# LSPACE-PCB.net
KiCad netlist of a schematic drawn in EAGLE
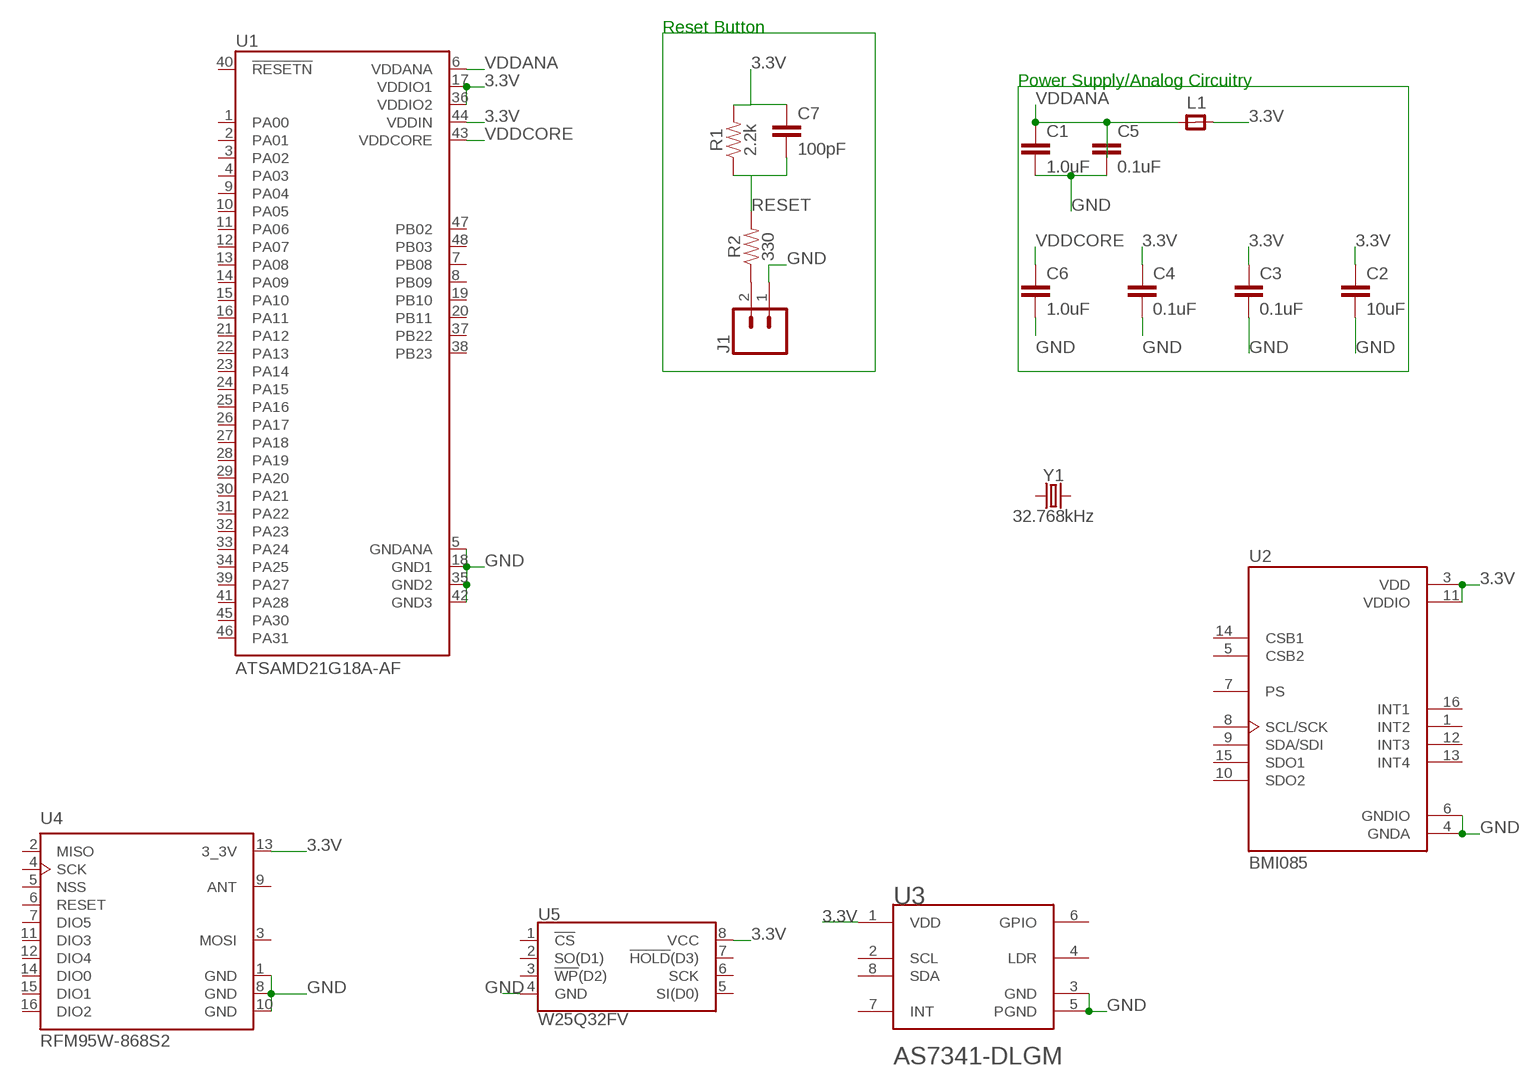
[diagram p0: schematic, sheet 1]

(export (version "E")
  (design (tool "Eeschema 10.0.6"))
  (components
    (comp (ref "C1")
      (value "1.0uF")
      (footprint "eagle-import:1206")
      (libsource (lib "eagle-import") (part "1.0UF-1206-50V-10%"))
    )
    (comp (ref "C2")
      (value "10uF")
      (footprint "eagle-import:1206")
      (libsource (lib "eagle-import") (part "10UF-1206-6.3V-20%"))
    )
    (comp (ref "C3")
      (value "0.1uF")
      (footprint "eagle-import:0603")
      (libsource (lib "eagle-import") (part "0.1UF-0603-100V-10%"))
    )
    (comp (ref "C4")
      (value "0.1uF")
      (footprint "eagle-import:0603")
      (libsource (lib "eagle-import") (part "0.1UF-0603-100V-10%"))
    )
    (comp (ref "C5")
      (value "0.1uF")
      (footprint "eagle-import:0603")
      (libsource (lib "eagle-import") (part "0.1UF-0603-100V-10%"))
    )
    (comp (ref "C6")
      (value "1.0uF")
      (footprint "eagle-import:1206")
      (libsource (lib "eagle-import") (part "1.0UF-1206-50V-10%"))
    )
    (comp (ref "C7")
      (value "100pF")
      (footprint "eagle-import:0603")
      (libsource (lib "eagle-import") (part "100PF-0603-50V-5%"))
    )
    (comp (ref "J1")
      (value "CONN_02")
      (footprint "eagle-import:1X02")
      (libsource (lib "eagle-import") (part "CONN_02"))
    )
    (comp (ref "L1")
      (value "RC-MASTER-SMD_FB_1206MP")
      (footprint "eagle-import:RC-MASTER-SMD_L1206MP")
      (libsource (lib "eagle-import") (part "RC-MASTER-SMD_FB_1206MP"))
    )
    (comp (ref "R1")
      (value "2.2k")
      (footprint "eagle-import:0603")
      (libsource (lib "eagle-import") (part "2.2KOHM-0603-1/10W-1%"))
    )
    (comp (ref "R2")
      (value "330")
      (footprint "eagle-import:0603")
      (libsource (lib "eagle-import") (part "330OHM-0603-1/10W-1%"))
    )
    (comp (ref "U1")
      (value "ATSAMD21G18A-AF")
      (footprint "eagle-import:QFP50P900X900X120-48N")
      (fields (field (name "MF") "Microchip Technology / Atmel"))
      (libsource (lib "eagle-import") (part "ATSAMD21G18A-AF"))
    )
    (comp (ref "U2")
      (value "BMI085")
      (footprint "eagle-import:PQFN50P450X300X100-16N")
      (fields (field (name "MF") "Bosch Sensortec"))
      (libsource (lib "eagle-import") (part "BMI085"))
    )
    (comp (ref "U3")
      (value "AMS_AS7341-DLGMAMS_AS7341-DLGM_0_0")
      (footprint "eagle-import:AMS_AS7341-DLGM_0")
      (fields
        (field (name "DIGIKEY_PART_NUMBER") "AS7341-DLGMCT-ND")
        (field (name "MF") "ams")
        (field (name "MOUSER_PART_NUMBER") "985-AS7341-DLGM")
      )
      (libsource (lib "eagle-import") (part "AMS_AS7341-DLGMAMS_AS7341-DLGM_0_0"))
    )
    (comp (ref "U4")
      (value "RFM95W-868S2")
      (footprint "eagle-import:XCVR_RFM95W-868S2")
      (fields (field (name "MF") "RF"))
      (libsource (lib "eagle-import") (part "RFM95W-868S2"))
    )
    (comp (ref "U5")
      (value "W25Q32FV")
      (footprint "eagle-import:SOIC-8")
      (libsource (lib "eagle-import") (part "W25Q32FVSS"))
    )
    (comp (ref "Y1")
      (value "32.768kHz")
      (footprint "eagle-import:CRYSTAL-SMD-3.2X1.5MM")
      (libsource (lib "eagle-import") (part "CRYSTAL-32.768KHZSMD-3.2X1.5"))
    )
  )
  (nets
    (net (code "1") (name "/3.3V") (class "Default")
      (node (ref "C2") (pin "1") (pinfunction "1_1") (pintype "passive"))
      (node (ref "C3") (pin "1") (pinfunction "1_1") (pintype "passive"))
      (node (ref "C4") (pin "1") (pinfunction "1_1") (pintype "passive"))
      (node (ref "C7") (pin "1") (pinfunction "1_1") (pintype "passive"))
      (node (ref "L1") (pin "2") (pinfunction "2_2") (pintype "passive"))
      (node (ref "R1") (pin "2") (pinfunction "2_2") (pintype "passive"))
      (node (ref "U1") (pin "17") (pinfunction "VDDIO1_17") (pintype "power_in"))
      (node (ref "U1") (pin "36") (pinfunction "VDDIO2_36") (pintype "power_in"))
      (node (ref "U1") (pin "44") (pinfunction "VDDIN_44") (pintype "power_in"))
      (node (ref "U2") (pin "11") (pinfunction "VDDIO_11") (pintype "power_in"))
      (node (ref "U2") (pin "3") (pinfunction "VDD_3") (pintype "power_in"))
      (node (ref "U3") (pin "1") (pinfunction "VDD_1") (pintype "power_in"))
      (node (ref "U4") (pin "13") (pinfunction "3_3V_13") (pintype "power_in"))
      (node (ref "U5") (pin "8") (pinfunction "VCC_8") (pintype "bidirectional"))
    )
    (net (code "2") (name "/GND") (class "Default")
      (node (ref "C1") (pin "2") (pinfunction "2_2") (pintype "passive"))
      (node (ref "C2") (pin "2") (pinfunction "2_2") (pintype "passive"))
      (node (ref "C3") (pin "2") (pinfunction "2_2") (pintype "passive"))
      (node (ref "C4") (pin "2") (pinfunction "2_2") (pintype "passive"))
      (node (ref "C5") (pin "2") (pinfunction "2_2") (pintype "passive"))
      (node (ref "C6") (pin "2") (pinfunction "2_2") (pintype "passive"))
      (node (ref "J1") (pin "1") (pinfunction "1_1") (pintype "passive"))
      (node (ref "U1") (pin "18") (pinfunction "GND1_18") (pintype "power_in"))
      (node (ref "U1") (pin "35") (pinfunction "GND2_35") (pintype "power_in"))
      (node (ref "U1") (pin "42") (pinfunction "GND3_42") (pintype "power_in"))
      (node (ref "U1") (pin "5") (pinfunction "GNDANA_5") (pintype "power_in"))
      (node (ref "U2") (pin "4") (pinfunction "GNDA_4") (pintype "power_in"))
      (node (ref "U2") (pin "6") (pinfunction "GNDIO_6") (pintype "power_in"))
      (node (ref "U3") (pin "3") (pinfunction "GND_3") (pintype "power_in"))
      (node (ref "U3") (pin "5") (pinfunction "PGND_5") (pintype "power_in"))
      (node (ref "U4") (pin "1") (pinfunction "GND_1") (pintype "power_in"))
      (node (ref "U4") (pin "10") (pinfunction "GND_10") (pintype "power_in"))
      (node (ref "U4") (pin "8") (pinfunction "GND_8") (pintype "power_in"))
      (node (ref "U5") (pin "4") (pinfunction "GND_4") (pintype "bidirectional"))
    )
    (net (code "3") (name "/RESET") (class "Default")
      (node (ref "C7") (pin "2") (pinfunction "2_2") (pintype "passive"))
      (node (ref "R1") (pin "1") (pinfunction "1_1") (pintype "passive"))
      (node (ref "R2") (pin "2") (pinfunction "2_2") (pintype "passive"))
    )
    (net (code "4") (name "/VDDANA") (class "Default")
      (node (ref "C1") (pin "1") (pinfunction "1_1") (pintype "passive"))
      (node (ref "C5") (pin "1") (pinfunction "1_1") (pintype "passive"))
      (node (ref "L1") (pin "1") (pinfunction "1_1") (pintype "passive"))
      (node (ref "U1") (pin "6") (pinfunction "VDDANA_6") (pintype "power_in"))
    )
    (net (code "5") (name "/VDDCORE") (class "Default")
      (node (ref "C6") (pin "1") (pinfunction "1_1") (pintype "passive"))
      (node (ref "U1") (pin "43") (pinfunction "VDDCORE_43") (pintype "power_in"))
    )
    (net (code "6") (name "Net-(J1-Pad2)") (class "Default")
      (node (ref "J1") (pin "2") (pinfunction "2_2") (pintype "passive"))
      (node (ref "R2") (pin "1") (pinfunction "1_1") (pintype "passive"))
    )
    (net (code "7") (name "unconnected-(U1-PA00-Pad1)") (class "Default")
      (node (ref "U1") (pin "1") (pinfunction "PA00_1") (pintype "bidirectional"))
    )
    (net (code "8") (name "unconnected-(U1-PA01-Pad2)") (class "Default")
      (node (ref "U1") (pin "2") (pinfunction "PA01_2") (pintype "bidirectional"))
    )
    (net (code "9") (name "unconnected-(U1-PA02-Pad3)") (class "Default")
      (node (ref "U1") (pin "3") (pinfunction "PA02_3") (pintype "bidirectional"))
    )
    (net (code "10") (name "unconnected-(U1-PA03-Pad4)") (class "Default")
      (node (ref "U1") (pin "4") (pinfunction "PA03_4") (pintype "bidirectional"))
    )
    (net (code "11") (name "unconnected-(U1-PA04-Pad9)") (class "Default")
      (node (ref "U1") (pin "9") (pinfunction "PA04_9") (pintype "bidirectional"))
    )
    (net (code "12") (name "unconnected-(U1-PA05-Pad10)") (class "Default")
      (node (ref "U1") (pin "10") (pinfunction "PA05_10") (pintype "bidirectional"))
    )
    (net (code "13") (name "unconnected-(U1-PA06-Pad11)") (class "Default")
      (node (ref "U1") (pin "11") (pinfunction "PA06_11") (pintype "bidirectional"))
    )
    (net (code "14") (name "unconnected-(U1-PA07-Pad12)") (class "Default")
      (node (ref "U1") (pin "12") (pinfunction "PA07_12") (pintype "bidirectional"))
    )
    (net (code "15") (name "unconnected-(U1-PA08-Pad13)") (class "Default")
      (node (ref "U1") (pin "13") (pinfunction "PA08_13") (pintype "bidirectional"))
    )
    (net (code "16") (name "unconnected-(U1-PA09-Pad14)") (class "Default")
      (node (ref "U1") (pin "14") (pinfunction "PA09_14") (pintype "bidirectional"))
    )
    (net (code "17") (name "unconnected-(U1-PA10-Pad15)") (class "Default")
      (node (ref "U1") (pin "15") (pinfunction "PA10_15") (pintype "bidirectional"))
    )
    (net (code "18") (name "unconnected-(U1-PA11-Pad16)") (class "Default")
      (node (ref "U1") (pin "16") (pinfunction "PA11_16") (pintype "bidirectional"))
    )
    (net (code "19") (name "unconnected-(U1-PA12-Pad21)") (class "Default")
      (node (ref "U1") (pin "21") (pinfunction "PA12_21") (pintype "bidirectional"))
    )
    (net (code "20") (name "unconnected-(U1-PA13-Pad22)") (class "Default")
      (node (ref "U1") (pin "22") (pinfunction "PA13_22") (pintype "bidirectional"))
    )
    (net (code "21") (name "unconnected-(U1-PA14-Pad23)") (class "Default")
      (node (ref "U1") (pin "23") (pinfunction "PA14_23") (pintype "bidirectional"))
    )
    (net (code "22") (name "unconnected-(U1-PA15-Pad24)") (class "Default")
      (node (ref "U1") (pin "24") (pinfunction "PA15_24") (pintype "bidirectional"))
    )
    (net (code "23") (name "unconnected-(U1-PA16-Pad25)") (class "Default")
      (node (ref "U1") (pin "25") (pinfunction "PA16_25") (pintype "bidirectional"))
    )
    (net (code "24") (name "unconnected-(U1-PA17-Pad26)") (class "Default")
      (node (ref "U1") (pin "26") (pinfunction "PA17_26") (pintype "bidirectional"))
    )
    (net (code "25") (name "unconnected-(U1-PA18-Pad27)") (class "Default")
      (node (ref "U1") (pin "27") (pinfunction "PA18_27") (pintype "bidirectional"))
    )
    (net (code "26") (name "unconnected-(U1-PA19-Pad28)") (class "Default")
      (node (ref "U1") (pin "28") (pinfunction "PA19_28") (pintype "bidirectional"))
    )
    (net (code "27") (name "unconnected-(U1-PA20-Pad29)") (class "Default")
      (node (ref "U1") (pin "29") (pinfunction "PA20_29") (pintype "bidirectional"))
    )
    (net (code "28") (name "unconnected-(U1-PA21-Pad30)") (class "Default")
      (node (ref "U1") (pin "30") (pinfunction "PA21_30") (pintype "bidirectional"))
    )
    (net (code "29") (name "unconnected-(U1-PA22-Pad31)") (class "Default")
      (node (ref "U1") (pin "31") (pinfunction "PA22_31") (pintype "bidirectional"))
    )
    (net (code "30") (name "unconnected-(U1-PA23-Pad32)") (class "Default")
      (node (ref "U1") (pin "32") (pinfunction "PA23_32") (pintype "bidirectional"))
    )
    (net (code "31") (name "unconnected-(U1-PA24-Pad33)") (class "Default")
      (node (ref "U1") (pin "33") (pinfunction "PA24_33") (pintype "bidirectional"))
    )
    (net (code "32") (name "unconnected-(U1-PA25-Pad34)") (class "Default")
      (node (ref "U1") (pin "34") (pinfunction "PA25_34") (pintype "bidirectional"))
    )
    (net (code "33") (name "unconnected-(U1-PA27-Pad39)") (class "Default")
      (node (ref "U1") (pin "39") (pinfunction "PA27_39") (pintype "bidirectional"))
    )
    (net (code "34") (name "unconnected-(U1-PA28-Pad41)") (class "Default")
      (node (ref "U1") (pin "41") (pinfunction "PA28_41") (pintype "bidirectional"))
    )
    (net (code "35") (name "unconnected-(U1-PA30-Pad45)") (class "Default")
      (node (ref "U1") (pin "45") (pinfunction "PA30_45") (pintype "bidirectional"))
    )
    (net (code "36") (name "unconnected-(U1-PA31-Pad46)") (class "Default")
      (node (ref "U1") (pin "46") (pinfunction "PA31_46") (pintype "bidirectional"))
    )
    (net (code "37") (name "unconnected-(U1-PB02-Pad47)") (class "Default")
      (node (ref "U1") (pin "47") (pinfunction "PB02_47") (pintype "bidirectional"))
    )
    (net (code "38") (name "unconnected-(U1-PB03-Pad48)") (class "Default")
      (node (ref "U1") (pin "48") (pinfunction "PB03_48") (pintype "bidirectional"))
    )
    (net (code "39") (name "unconnected-(U1-PB08-Pad7)") (class "Default")
      (node (ref "U1") (pin "7") (pinfunction "PB08_7") (pintype "bidirectional"))
    )
    (net (code "40") (name "unconnected-(U1-PB09-Pad8)") (class "Default")
      (node (ref "U1") (pin "8") (pinfunction "PB09_8") (pintype "bidirectional"))
    )
    (net (code "41") (name "unconnected-(U1-PB10-Pad19)") (class "Default")
      (node (ref "U1") (pin "19") (pinfunction "PB10_19") (pintype "bidirectional"))
    )
    (net (code "42") (name "unconnected-(U1-PB11-Pad20)") (class "Default")
      (node (ref "U1") (pin "20") (pinfunction "PB11_20") (pintype "bidirectional"))
    )
    (net (code "43") (name "unconnected-(U1-PB22-Pad37)") (class "Default")
      (node (ref "U1") (pin "37") (pinfunction "PB22_37") (pintype "bidirectional"))
    )
    (net (code "44") (name "unconnected-(U1-PB23-Pad38)") (class "Default")
      (node (ref "U1") (pin "38") (pinfunction "PB23_38") (pintype "bidirectional"))
    )
    (net (code "45") (name "unconnected-(U1-~{RESETN}-Pad40)") (class "Default")
      (node (ref "U1") (pin "40") (pinfunction "~{RESETN}_40") (pintype "input"))
    )
    (net (code "46") (name "unconnected-(U2-CSB1-Pad14)") (class "Default")
      (node (ref "U2") (pin "14") (pinfunction "CSB1_14") (pintype "input"))
    )
    (net (code "47") (name "unconnected-(U2-CSB2-Pad5)") (class "Default")
      (node (ref "U2") (pin "5") (pinfunction "CSB2_5") (pintype "input"))
    )
    (net (code "48") (name "unconnected-(U2-INT1-Pad16)") (class "Default")
      (node (ref "U2") (pin "16") (pinfunction "INT1_16") (pintype "bidirectional"))
    )
    (net (code "49") (name "unconnected-(U2-INT2-Pad1)") (class "Default")
      (node (ref "U2") (pin "1") (pinfunction "INT2_1") (pintype "bidirectional"))
    )
    (net (code "50") (name "unconnected-(U2-INT3-Pad12)") (class "Default")
      (node (ref "U2") (pin "12") (pinfunction "INT3_12") (pintype "bidirectional"))
    )
    (net (code "51") (name "unconnected-(U2-INT4-Pad13)") (class "Default")
      (node (ref "U2") (pin "13") (pinfunction "INT4_13") (pintype "bidirectional"))
    )
    (net (code "52") (name "unconnected-(U2-PS-Pad7)") (class "Default")
      (node (ref "U2") (pin "7") (pinfunction "PS_7") (pintype "input"))
    )
    (net (code "53") (name "unconnected-(U2-SCL{slash}SCK-Pad8)") (class "Default")
      (node (ref "U2") (pin "8") (pinfunction "SCL/SCK_8") (pintype "input"))
    )
    (net (code "54") (name "unconnected-(U2-SDA{slash}SDI-Pad9)") (class "Default")
      (node (ref "U2") (pin "9") (pinfunction "SDA/SDI_9") (pintype "bidirectional"))
    )
    (net (code "55") (name "unconnected-(U2-SDO1-Pad15)") (class "Default")
      (node (ref "U2") (pin "15") (pinfunction "SDO1_15") (pintype "output"))
    )
    (net (code "56") (name "unconnected-(U2-SDO2-Pad10)") (class "Default")
      (node (ref "U2") (pin "10") (pinfunction "SDO2_10") (pintype "output"))
    )
    (net (code "57") (name "unconnected-(U3-GPIO-Pad6)") (class "Default")
      (node (ref "U3") (pin "6") (pinfunction "GPIO_6") (pintype "bidirectional"))
    )
    (net (code "58") (name "unconnected-(U3-INT-Pad7)") (class "Default")
      (node (ref "U3") (pin "7") (pinfunction "INT_7") (pintype "output"))
    )
    (net (code "59") (name "unconnected-(U3-LDR-Pad4)") (class "Default")
      (node (ref "U3") (pin "4") (pinfunction "LDR_4") (pintype "input"))
    )
    (net (code "60") (name "unconnected-(U3-SCL-Pad2)") (class "Default")
      (node (ref "U3") (pin "2") (pinfunction "SCL_2") (pintype "bidirectional"))
    )
    (net (code "61") (name "unconnected-(U3-SDA-Pad8)") (class "Default")
      (node (ref "U3") (pin "8") (pinfunction "SDA_8") (pintype "bidirectional"))
    )
    (net (code "62") (name "unconnected-(U4-ANT-Pad9)") (class "Default")
      (node (ref "U4") (pin "9") (pinfunction "ANT_9") (pintype "passive"))
    )
    (net (code "63") (name "unconnected-(U4-DIO0-Pad14)") (class "Default")
      (node (ref "U4") (pin "14") (pinfunction "DIO0_14") (pintype "bidirectional"))
    )
    (net (code "64") (name "unconnected-(U4-DIO1-Pad15)") (class "Default")
      (node (ref "U4") (pin "15") (pinfunction "DIO1_15") (pintype "bidirectional"))
    )
    (net (code "65") (name "unconnected-(U4-DIO2-Pad16)") (class "Default")
      (node (ref "U4") (pin "16") (pinfunction "DIO2_16") (pintype "bidirectional"))
    )
    (net (code "66") (name "unconnected-(U4-DIO3-Pad11)") (class "Default")
      (node (ref "U4") (pin "11") (pinfunction "DIO3_11") (pintype "bidirectional"))
    )
    (net (code "67") (name "unconnected-(U4-DIO4-Pad12)") (class "Default")
      (node (ref "U4") (pin "12") (pinfunction "DIO4_12") (pintype "bidirectional"))
    )
    (net (code "68") (name "unconnected-(U4-DIO5-Pad7)") (class "Default")
      (node (ref "U4") (pin "7") (pinfunction "DIO5_7") (pintype "bidirectional"))
    )
    (net (code "69") (name "unconnected-(U4-MISO-Pad2)") (class "Default")
      (node (ref "U4") (pin "2") (pinfunction "MISO_2") (pintype "input"))
    )
    (net (code "70") (name "unconnected-(U4-MOSI-Pad3)") (class "Default")
      (node (ref "U4") (pin "3") (pinfunction "MOSI_3") (pintype "output"))
    )
    (net (code "71") (name "unconnected-(U4-NSS-Pad5)") (class "Default")
      (node (ref "U4") (pin "5") (pinfunction "NSS_5") (pintype "input"))
    )
    (net (code "72") (name "unconnected-(U4-RESET-Pad6)") (class "Default")
      (node (ref "U4") (pin "6") (pinfunction "RESET_6") (pintype "bidirectional"))
    )
    (net (code "73") (name "unconnected-(U4-SCK-Pad4)") (class "Default")
      (node (ref "U4") (pin "4") (pinfunction "SCK_4") (pintype "input"))
    )
    (net (code "74") (name "unconnected-(U5-SCK-Pad6)") (class "Default")
      (node (ref "U5") (pin "6") (pinfunction "SCK_6") (pintype "bidirectional"))
    )
    (net (code "75") (name "unconnected-(U5-SI(D0)-Pad5)") (class "Default")
      (node (ref "U5") (pin "5") (pinfunction "SI(D0)_5") (pintype "bidirectional"))
    )
    (net (code "76") (name "unconnected-(U5-SO(D1)-Pad2)") (class "Default")
      (node (ref "U5") (pin "2") (pinfunction "SO(D1)_2") (pintype "bidirectional"))
    )
    (net (code "77") (name "unconnected-(U5-~{CS}-Pad1)") (class "Default")
      (node (ref "U5") (pin "1") (pinfunction "~{CS}_1") (pintype "bidirectional"))
    )
    (net (code "78") (name "unconnected-(U5-~{HOLD}(D3)-Pad7)") (class "Default")
      (node (ref "U5") (pin "7") (pinfunction "~{HOLD}(D3)_7") (pintype "bidirectional"))
    )
    (net (code "79") (name "unconnected-(U5-~{WP}(D2)-Pad3)") (class "Default")
      (node (ref "U5") (pin "3") (pinfunction "~{WP}(D2)_3") (pintype "bidirectional"))
    )
    (net (code "80") (name "unconnected-(Y1-1-PadP$1)") (class "Default")
      (node (ref "Y1") (pin "P$1") (pinfunction "1_P$1") (pintype "passive"))
    )
    (net (code "81") (name "unconnected-(Y1-2-PadP$2)") (class "Default")
      (node (ref "Y1") (pin "P$2") (pinfunction "2_P$2") (pintype "passive"))
    )
  )
)
